# LEDs2.net
KiCad netlist of a schematic drawn in EAGLE
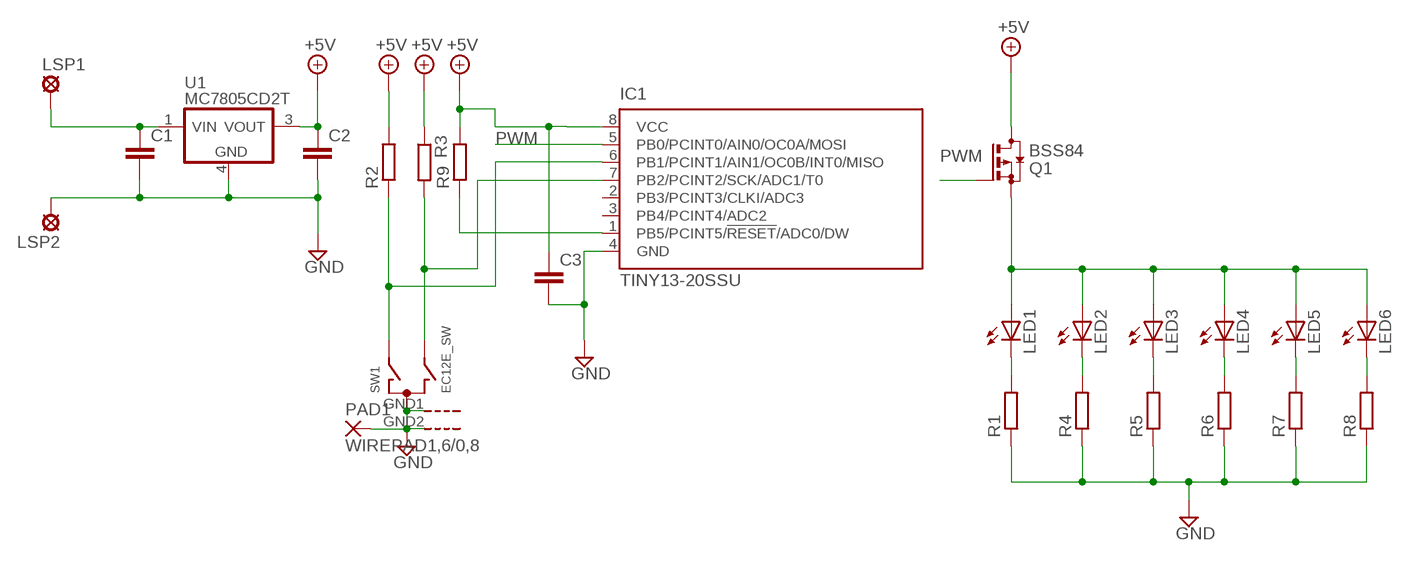
[diagram p0: schematic, sheet 1]

(export (version "E")
  (design (tool "Eeschema 10.0.6"))
  (components
    (comp (ref "C1")
      (value "C-EUC1206K")
      (footprint "eagle-import:C1206K")
      (libsource (lib "eagle-import") (part "C-EUC1206K"))
    )
    (comp (ref "C2")
      (value "C-EUC1206K")
      (footprint "eagle-import:C1206K")
      (libsource (lib "eagle-import") (part "C-EUC1206K"))
    )
    (comp (ref "C3")
      (value "C-EUC1206K")
      (footprint "eagle-import:C1206K")
      (libsource (lib "eagle-import") (part "C-EUC1206K"))
    )
    (comp (ref "IC1")
      (value "TINY13-20SSU")
      (footprint "eagle-import:8S1")
      (fields (field (name "MPN") "ATTINY13-20SSU"))
      (libsource (lib "eagle-import") (part "TINY13SSU-20"))
    )
    (comp (ref "LED1")
      (value "LED-2AC-CP41B-WES")
      (footprint "eagle-import:CP41B")
      (libsource (lib "eagle-import") (part "LED-2AC-CP41B-WES"))
    )
    (comp (ref "LED2")
      (value "LED-2AC-CP41B-WES")
      (footprint "eagle-import:CP41B")
      (libsource (lib "eagle-import") (part "LED-2AC-CP41B-WES"))
    )
    (comp (ref "LED3")
      (value "LED-2AC-CP41B-WES")
      (footprint "eagle-import:CP41B")
      (libsource (lib "eagle-import") (part "LED-2AC-CP41B-WES"))
    )
    (comp (ref "LED4")
      (value "LED-2AC-CP41B-WES")
      (footprint "eagle-import:CP41B")
      (libsource (lib "eagle-import") (part "LED-2AC-CP41B-WES"))
    )
    (comp (ref "LED5")
      (value "LED-2AC-CP41B-WES")
      (footprint "eagle-import:CP41B")
      (libsource (lib "eagle-import") (part "LED-2AC-CP41B-WES"))
    )
    (comp (ref "LED6")
      (value "LED-2AC-CP41B-WES")
      (footprint "eagle-import:CP41B")
      (libsource (lib "eagle-import") (part "LED-2AC-CP41B-WES"))
    )
    (comp (ref "LSP1")
      (value "LSP10")
      (footprint "eagle-import:LSP10")
      (libsource (lib "eagle-import") (part "LSP10"))
    )
    (comp (ref "LSP2")
      (value "LSP10")
      (footprint "eagle-import:LSP10")
      (libsource (lib "eagle-import") (part "LSP10"))
    )
    (comp (ref "PAD1")
      (value "WIREPAD1,6/0,8")
      (footprint "eagle-import:1,6_0,8")
      (libsource (lib "eagle-import") (part "WIREPAD1,6/0,8"))
    )
    (comp (ref "Q1")
      (value "BSS84")
      (footprint "eagle-import:SOT23")
      (libsource (lib "eagle-import") (part "BSS84"))
    )
    (comp (ref "R1")
      (value "R-EU_M0805")
      (footprint "eagle-import:M0805")
      (libsource (lib "eagle-import") (part "R-EU_M0805"))
    )
    (comp (ref "R2")
      (value "R-EU_M1206")
      (footprint "eagle-import:M1206")
      (libsource (lib "eagle-import") (part "R-EU_M1206"))
    )
    (comp (ref "R3")
      (value "R-EU_M1206")
      (footprint "eagle-import:M1206")
      (libsource (lib "eagle-import") (part "R-EU_M1206"))
    )
    (comp (ref "R4")
      (value "R-EU_M0805")
      (footprint "eagle-import:M0805")
      (libsource (lib "eagle-import") (part "R-EU_M0805"))
    )
    (comp (ref "R5")
      (value "R-EU_M0805")
      (footprint "eagle-import:M0805")
      (libsource (lib "eagle-import") (part "R-EU_M0805"))
    )
    (comp (ref "R6")
      (value "R-EU_M0805")
      (footprint "eagle-import:M0805")
      (libsource (lib "eagle-import") (part "R-EU_M0805"))
    )
    (comp (ref "R7")
      (value "R-EU_M0805")
      (footprint "eagle-import:M0805")
      (libsource (lib "eagle-import") (part "R-EU_M0805"))
    )
    (comp (ref "R8")
      (value "R-EU_M0805")
      (footprint "eagle-import:M0805")
      (libsource (lib "eagle-import") (part "R-EU_M0805"))
    )
    (comp (ref "R9")
      (value "R-EU_M0805")
      (footprint "eagle-import:M0805")
      (libsource (lib "eagle-import") (part "R-EU_M0805"))
    )
    (comp (ref "SW1")
      (value "EC12E_SW")
      (footprint "eagle-import:ALPS_EC12E_SW")
      (fields (field (name "MPN") "EC12E2424407"))
      (libsource (lib "eagle-import") (part "EC12E_SW"))
    )
    (comp (ref "U1")
      (value "MC7805CD2T")
      (footprint "eagle-import:D2PAK-3")
      (libsource (lib "eagle-import") (part "MC78D2T05C"))
    )
  )
  (nets
    (net (code "1") (name "+5V") (class "Default")
      (node (ref "C2") (pin "1") (pinfunction "1_1") (pintype "passive"))
      (node (ref "C3") (pin "1") (pinfunction "1_1") (pintype "passive"))
      (node (ref "IC1") (pin "8") (pinfunction "VCC_8") (pintype "power_in"))
      (node (ref "Q1") (pin "3") (pinfunction "D_3") (pintype "passive"))
      (node (ref "R2") (pin "2") (pinfunction "2_2") (pintype "passive"))
      (node (ref "R3") (pin "1") (pinfunction "1_1") (pintype "passive"))
      (node (ref "R9") (pin "2") (pinfunction "2_2") (pintype "passive"))
      (node (ref "U1") (pin "3") (pinfunction "VOUT_3") (pintype "power_in"))
    )
    (net (code "2") (name "/PWM") (class "Default")
      (node (ref "IC1") (pin "5") (pinfunction "PB0/PCINT0/AIN0/OC0A/MOSI_5") (pintype "bidirectional"))
      (node (ref "Q1") (pin "1") (pinfunction "G_1") (pintype "passive"))
    )
    (net (code "3") (name "GND") (class "Default")
      (node (ref "C1") (pin "2") (pinfunction "2_2") (pintype "passive"))
      (node (ref "C2") (pin "2") (pinfunction "2_2") (pintype "passive"))
      (node (ref "C3") (pin "2") (pinfunction "2_2") (pintype "passive"))
      (node (ref "IC1") (pin "4") (pinfunction "GND_4") (pintype "power_in"))
      (node (ref "LSP2") (pin "MP") (pinfunction "MP_MP") (pintype "passive"))
      (node (ref "PAD1") (pin "1") (pinfunction "P_1") (pintype "passive"))
      (node (ref "R1") (pin "1") (pinfunction "1_1") (pintype "passive"))
      (node (ref "R4") (pin "1") (pinfunction "1_1") (pintype "passive"))
      (node (ref "R5") (pin "1") (pinfunction "1_1") (pintype "passive"))
      (node (ref "R6") (pin "1") (pinfunction "1_1") (pintype "passive"))
      (node (ref "R7") (pin "1") (pinfunction "1_1") (pintype "passive"))
      (node (ref "R8") (pin "1") (pinfunction "1_1") (pintype "passive"))
      (node (ref "SW1") (pin "C") (pinfunction "C_C") (pintype "passive"))
      (node (ref "SW1") (pin "GND1") (pinfunction "G_GND1") (pintype "passive"))
      (node (ref "SW1") (pin "GND2") (pinfunction "G_GND2") (pintype "passive"))
      (node (ref "U1") (pin "4") (pinfunction "GND_4") (pintype "power_in"))
    )
    (net (code "4") (name "Net-(IC1-PB1{slash}PCINT1{slash}AIN1{slash}OC0B{slash}INT0{slash}MISO)") (class "Default")
      (node (ref "IC1") (pin "6") (pinfunction "PB1/PCINT1/AIN1/OC0B/INT0/MISO_6") (pintype "bidirectional"))
      (node (ref "R2") (pin "1") (pinfunction "1_1") (pintype "passive"))
      (node (ref "SW1") (pin "A") (pinfunction "A_A") (pintype "passive"))
    )
    (net (code "5") (name "Net-(IC1-PB2{slash}PCINT2{slash}SCK{slash}ADC1{slash}T0)") (class "Default")
      (node (ref "IC1") (pin "7") (pinfunction "PB2/PCINT2/SCK/ADC1/T0_7") (pintype "bidirectional"))
      (node (ref "R3") (pin "2") (pinfunction "2_2") (pintype "passive"))
      (node (ref "SW1") (pin "B") (pinfunction "B_B") (pintype "passive"))
    )
    (net (code "6") (name "Net-(IC1-PB5{slash}PCINT5{slash}~{RESET}{slash}ADC0{slash}DW)") (class "Default")
      (node (ref "IC1") (pin "1") (pinfunction "PB5/PCINT5/~{RESET}/ADC0/DW_1") (pintype "bidirectional"))
      (node (ref "R9") (pin "1") (pinfunction "1_1") (pintype "passive"))
    )
    (net (code "7") (name "Net-(LED1-C-Pad1)") (class "Default")
      (node (ref "LED1") (pin "1") (pinfunction "C_1") (pintype "passive"))
      (node (ref "LED1") (pin "4") (pinfunction "C_4") (pintype "passive"))
      (node (ref "R1") (pin "2") (pinfunction "2_2") (pintype "passive"))
    )
    (net (code "8") (name "Net-(LED2-C-Pad1)") (class "Default")
      (node (ref "LED2") (pin "1") (pinfunction "C_1") (pintype "passive"))
      (node (ref "LED2") (pin "4") (pinfunction "C_4") (pintype "passive"))
      (node (ref "R4") (pin "2") (pinfunction "2_2") (pintype "passive"))
    )
    (net (code "9") (name "Net-(LED3-C-Pad1)") (class "Default")
      (node (ref "LED3") (pin "1") (pinfunction "C_1") (pintype "passive"))
      (node (ref "LED3") (pin "4") (pinfunction "C_4") (pintype "passive"))
      (node (ref "R5") (pin "2") (pinfunction "2_2") (pintype "passive"))
    )
    (net (code "10") (name "Net-(LED4-C-Pad1)") (class "Default")
      (node (ref "LED4") (pin "1") (pinfunction "C_1") (pintype "passive"))
      (node (ref "LED4") (pin "4") (pinfunction "C_4") (pintype "passive"))
      (node (ref "R6") (pin "2") (pinfunction "2_2") (pintype "passive"))
    )
    (net (code "11") (name "Net-(LED5-C-Pad1)") (class "Default")
      (node (ref "LED5") (pin "1") (pinfunction "C_1") (pintype "passive"))
      (node (ref "LED5") (pin "4") (pinfunction "C_4") (pintype "passive"))
      (node (ref "R7") (pin "2") (pinfunction "2_2") (pintype "passive"))
    )
    (net (code "12") (name "Net-(LED6-C-Pad1)") (class "Default")
      (node (ref "LED6") (pin "1") (pinfunction "C_1") (pintype "passive"))
      (node (ref "LED6") (pin "4") (pinfunction "C_4") (pintype "passive"))
      (node (ref "R8") (pin "2") (pinfunction "2_2") (pintype "passive"))
    )
    (net (code "13") (name "Net-(Q1-S)") (class "Default")
      (node (ref "LED1") (pin "2") (pinfunction "A_2") (pintype "passive"))
      (node (ref "LED1") (pin "3") (pinfunction "A_3") (pintype "passive"))
      (node (ref "LED2") (pin "2") (pinfunction "A_2") (pintype "passive"))
      (node (ref "LED2") (pin "3") (pinfunction "A_3") (pintype "passive"))
      (node (ref "LED3") (pin "2") (pinfunction "A_2") (pintype "passive"))
      (node (ref "LED3") (pin "3") (pinfunction "A_3") (pintype "passive"))
      (node (ref "LED4") (pin "2") (pinfunction "A_2") (pintype "passive"))
      (node (ref "LED4") (pin "3") (pinfunction "A_3") (pintype "passive"))
      (node (ref "LED5") (pin "2") (pinfunction "A_2") (pintype "passive"))
      (node (ref "LED5") (pin "3") (pinfunction "A_3") (pintype "passive"))
      (node (ref "LED6") (pin "2") (pinfunction "A_2") (pintype "passive"))
      (node (ref "LED6") (pin "3") (pinfunction "A_3") (pintype "passive"))
      (node (ref "Q1") (pin "2") (pinfunction "S_2") (pintype "passive"))
    )
    (net (code "14") (name "Net-(U1-VIN)") (class "Default")
      (node (ref "C1") (pin "1") (pinfunction "1_1") (pintype "passive"))
      (node (ref "LSP1") (pin "MP") (pinfunction "MP_MP") (pintype "passive"))
      (node (ref "U1") (pin "1") (pinfunction "VIN_1") (pintype "power_in"))
    )
    (net (code "15") (name "unconnected-(IC1-PB3{slash}PCINT3{slash}CLKI{slash}ADC3-Pad2)") (class "Default")
      (node (ref "IC1") (pin "2") (pinfunction "PB3/PCINT3/CLKI/ADC3_2") (pintype "bidirectional"))
    )
    (net (code "16") (name "unconnected-(IC1-PB4{slash}PCINT4{slash}ADC2-Pad3)") (class "Default")
      (node (ref "IC1") (pin "3") (pinfunction "PB4/PCINT4/ADC2_3") (pintype "bidirectional"))
    )
  )
)
